# LED_Canton_Tower.net
KiCad netlist of a schematic drawn in EasyEDA
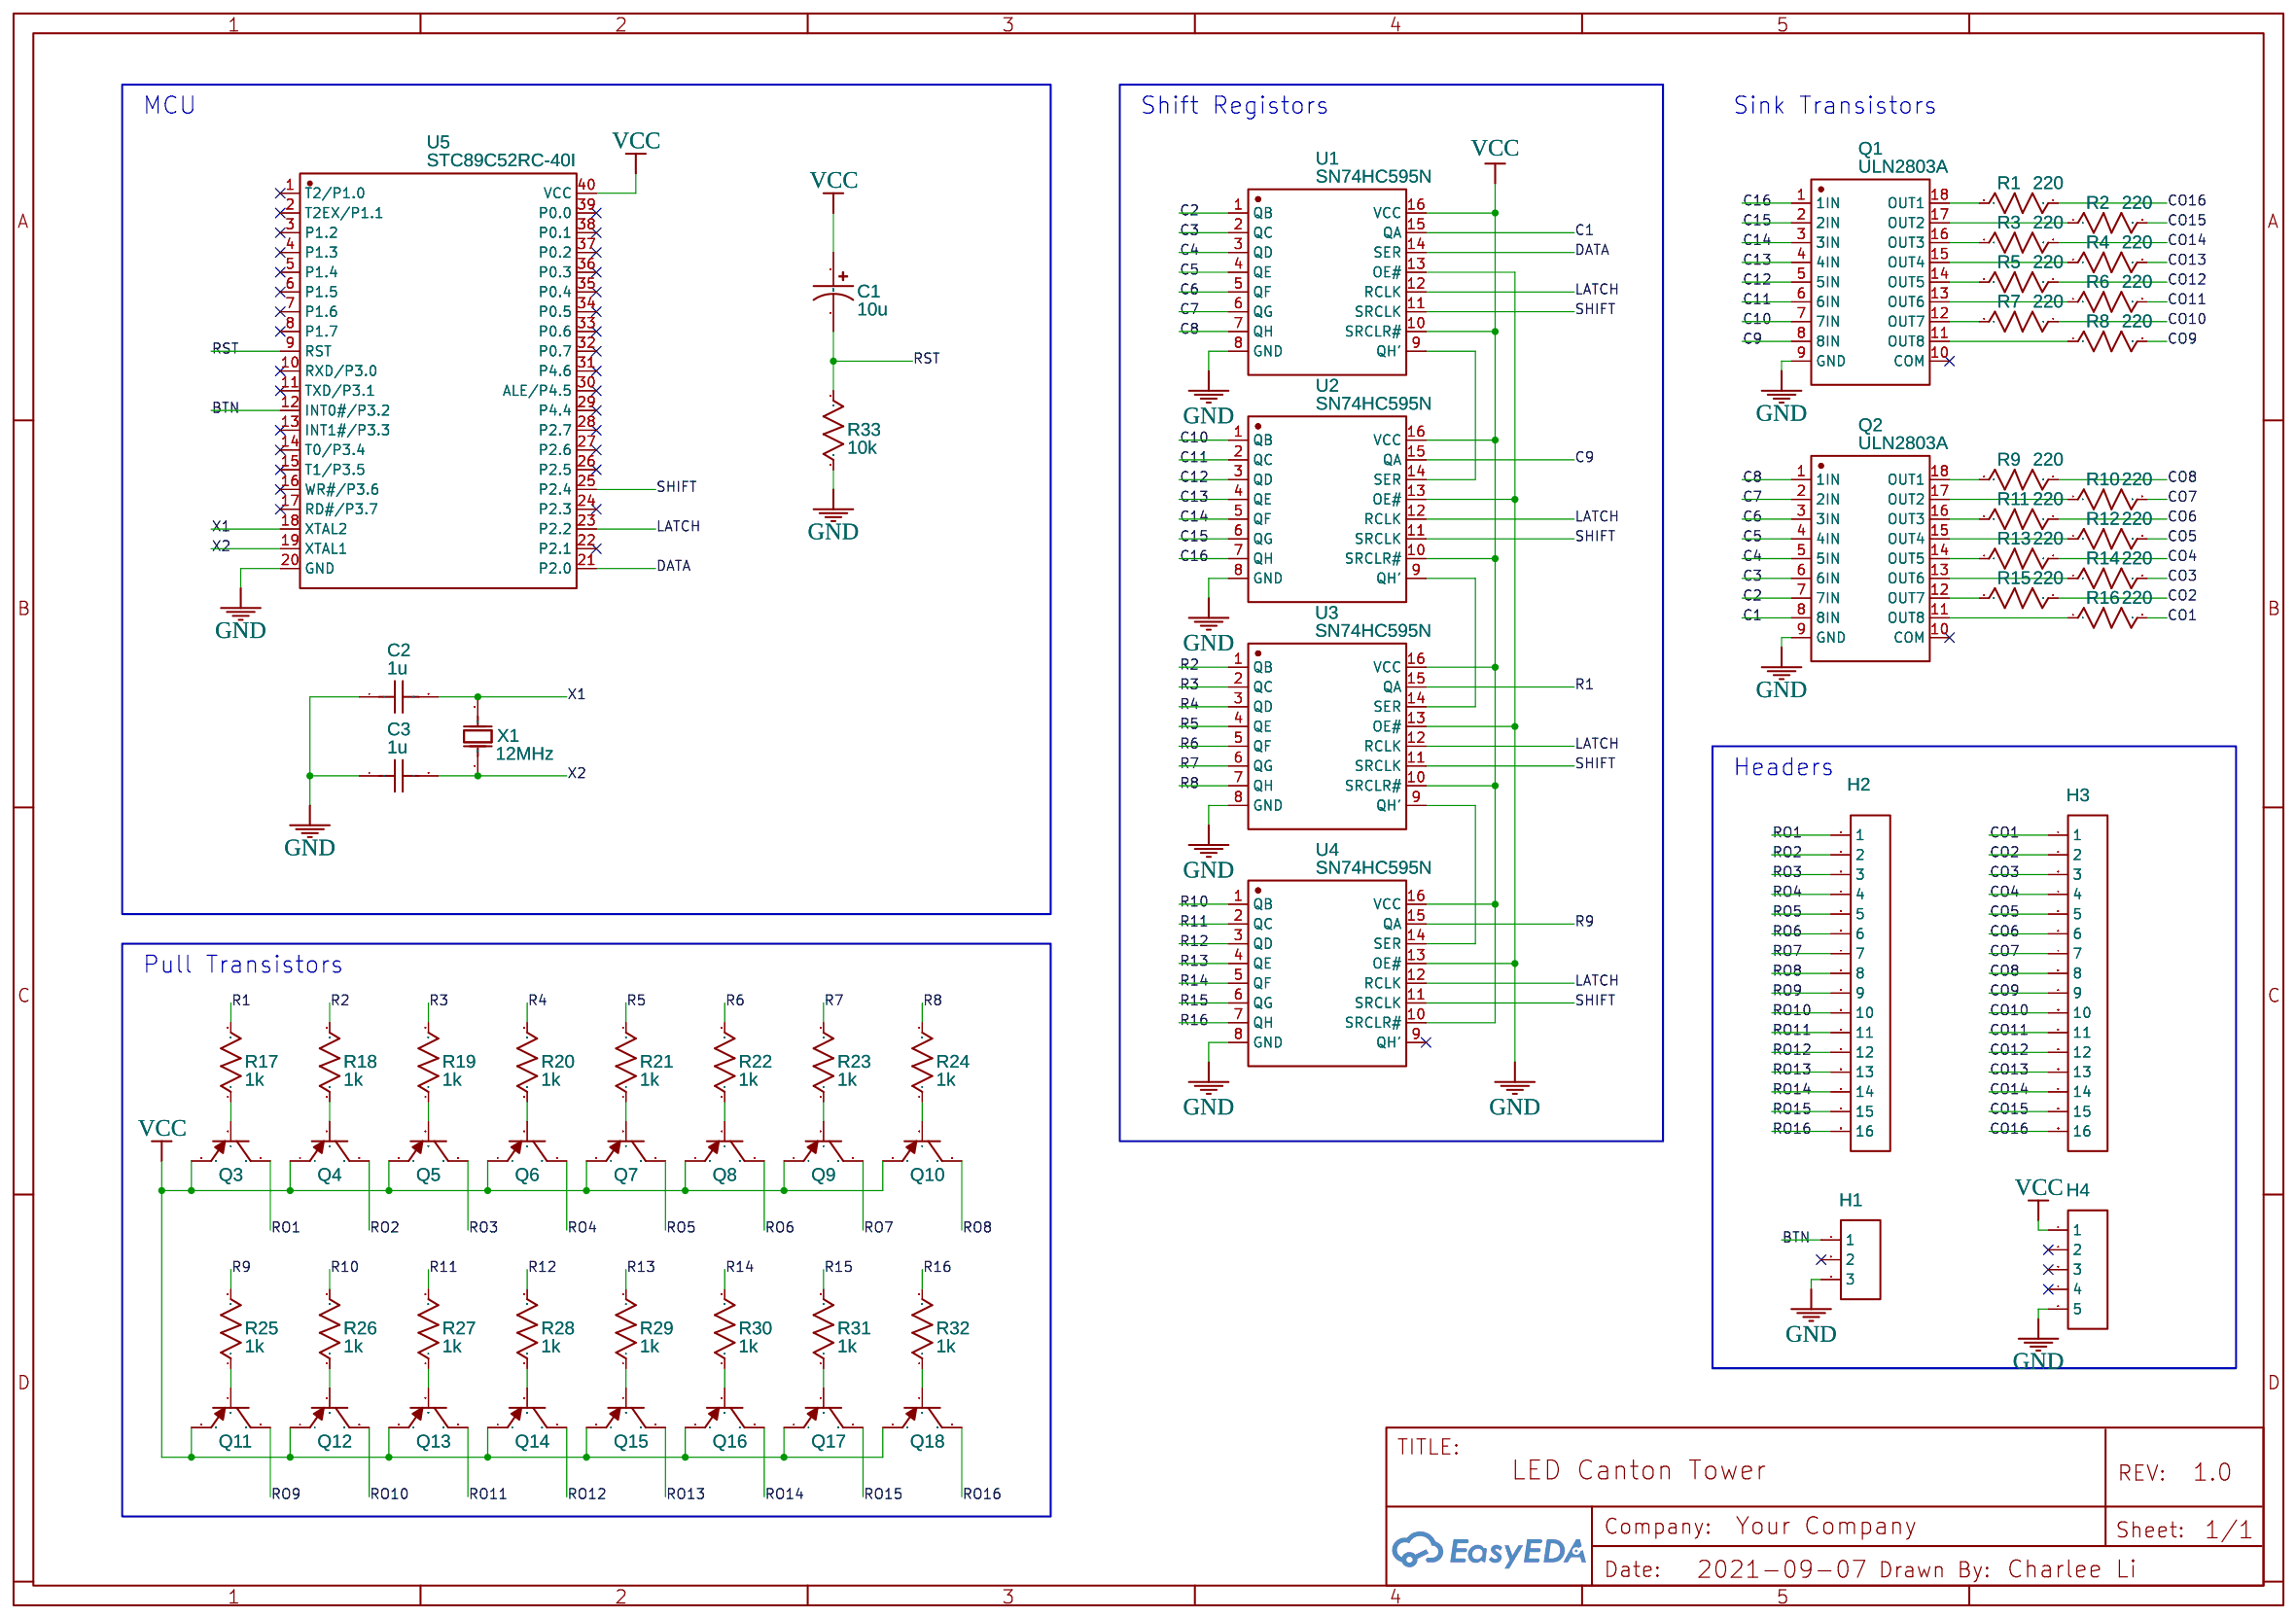
[diagram p0: schematic sheet]

(export (version "E")
  (design (tool "Eeschema 10.0.6"))
  (components
    (comp (ref "C1") (value "10u") (libsource (lib "") (part "CE_TH_D3.0×F1.5_US")))
    (comp (ref "C2") (value "1u") (libsource (lib "") (part "C_RAD-0.1_US")))
    (comp (ref "C3") (value "1u") (libsource (lib "") (part "C_RAD-0.1_US")))
    (comp (ref "H1")
      (value "HDR-F-2.54_1x3")
      (fields (field (name "BOM_Supplier Part") "C146690"))
      (libsource (lib "") (part "HDR-F-2.54_1x3"))
    )
    (comp (ref "H2")
      (value "HDR-F-2.54_1x16")
      (fields (field (name "BOM_Supplier Part") "C66987"))
      (libsource (lib "") (part "HDR-F-2.54_1x16"))
    )
    (comp (ref "H3")
      (value "HDR-F-2.54_1x16")
      (fields (field (name "BOM_Supplier Part") "C66987"))
      (libsource (lib "") (part "HDR-F-2.54_1x16"))
    )
    (comp (ref "H4")
      (value "HDR-F-2.54_1x5")
      (fields (field (name "BOM_Supplier Part") "C50950"))
      (libsource (lib "") (part "HDR-F-2.54_1x5"))
    )
    (comp (ref "Q1")
      (value "ULN2803A")
      (fields (field (name "BOM_Supplier Part") "C73936"))
      (libsource (lib "") (part "ULN2803A"))
    )
    (comp (ref "Q2")
      (value "ULN2803A")
      (fields (field (name "BOM_Supplier Part") "C73936"))
      (libsource (lib "") (part "ULN2803A"))
    )
    (comp (ref "Q3")
      (value "2N3906(TO-92)")
      (fields (field (name "BOM_Manufacturer Part") "2N3906") (field (name "BOM_Supplier Part") "C9809"))
      (libsource (lib "") (part "2N3906(TO-92)"))
    )
    (comp (ref "Q4")
      (value "2N3906(TO-92)")
      (fields (field (name "BOM_Manufacturer Part") "2N3906") (field (name "BOM_Supplier Part") "C9809"))
      (libsource (lib "") (part "2N3906(TO-92)"))
    )
    (comp (ref "Q5")
      (value "2N3906(TO-92)")
      (fields (field (name "BOM_Manufacturer Part") "2N3906") (field (name "BOM_Supplier Part") "C9809"))
      (libsource (lib "") (part "2N3906(TO-92)"))
    )
    (comp (ref "Q6")
      (value "2N3906(TO-92)")
      (fields (field (name "BOM_Manufacturer Part") "2N3906") (field (name "BOM_Supplier Part") "C9809"))
      (libsource (lib "") (part "2N3906(TO-92)"))
    )
    (comp (ref "Q7")
      (value "2N3906(TO-92)")
      (fields (field (name "BOM_Manufacturer Part") "2N3906") (field (name "BOM_Supplier Part") "C9809"))
      (libsource (lib "") (part "2N3906(TO-92)"))
    )
    (comp (ref "Q8")
      (value "2N3906(TO-92)")
      (fields (field (name "BOM_Manufacturer Part") "2N3906") (field (name "BOM_Supplier Part") "C9809"))
      (libsource (lib "") (part "2N3906(TO-92)"))
    )
    (comp (ref "Q9")
      (value "2N3906(TO-92)")
      (fields (field (name "BOM_Manufacturer Part") "2N3906") (field (name "BOM_Supplier Part") "C9809"))
      (libsource (lib "") (part "2N3906(TO-92)"))
    )
    (comp (ref "Q10")
      (value "2N3906(TO-92)")
      (fields (field (name "BOM_Manufacturer Part") "2N3906") (field (name "BOM_Supplier Part") "C9809"))
      (libsource (lib "") (part "2N3906(TO-92)"))
    )
    (comp (ref "Q11")
      (value "2N3906(TO-92)")
      (fields (field (name "BOM_Manufacturer Part") "2N3906") (field (name "BOM_Supplier Part") "C9809"))
      (libsource (lib "") (part "2N3906(TO-92)"))
    )
    (comp (ref "Q12")
      (value "2N3906(TO-92)")
      (fields (field (name "BOM_Manufacturer Part") "2N3906") (field (name "BOM_Supplier Part") "C9809"))
      (libsource (lib "") (part "2N3906(TO-92)"))
    )
    (comp (ref "Q13")
      (value "2N3906(TO-92)")
      (fields (field (name "BOM_Manufacturer Part") "2N3906") (field (name "BOM_Supplier Part") "C9809"))
      (libsource (lib "") (part "2N3906(TO-92)"))
    )
    (comp (ref "Q14")
      (value "2N3906(TO-92)")
      (fields (field (name "BOM_Manufacturer Part") "2N3906") (field (name "BOM_Supplier Part") "C9809"))
      (libsource (lib "") (part "2N3906(TO-92)"))
    )
    (comp (ref "Q15")
      (value "2N3906(TO-92)")
      (fields (field (name "BOM_Manufacturer Part") "2N3906") (field (name "BOM_Supplier Part") "C9809"))
      (libsource (lib "") (part "2N3906(TO-92)"))
    )
    (comp (ref "Q16")
      (value "2N3906(TO-92)")
      (fields (field (name "BOM_Manufacturer Part") "2N3906") (field (name "BOM_Supplier Part") "C9809"))
      (libsource (lib "") (part "2N3906(TO-92)"))
    )
    (comp (ref "Q17")
      (value "2N3906(TO-92)")
      (fields (field (name "BOM_Manufacturer Part") "2N3906") (field (name "BOM_Supplier Part") "C9809"))
      (libsource (lib "") (part "2N3906(TO-92)"))
    )
    (comp (ref "Q18")
      (value "2N3906(TO-92)")
      (fields (field (name "BOM_Manufacturer Part") "2N3906") (field (name "BOM_Supplier Part") "C9809"))
      (libsource (lib "") (part "2N3906(TO-92)"))
    )
    (comp (ref "R1") (value "220") (libsource (lib "") (part "R_AXIAL-0.3_US")))
    (comp (ref "R2") (value "220") (libsource (lib "") (part "R_AXIAL-0.3_US")))
    (comp (ref "R3") (value "220") (libsource (lib "") (part "R_AXIAL-0.3_US")))
    (comp (ref "R4") (value "220") (libsource (lib "") (part "R_AXIAL-0.3_US")))
    (comp (ref "R5") (value "220") (libsource (lib "") (part "R_AXIAL-0.3_US")))
    (comp (ref "R6") (value "220") (libsource (lib "") (part "R_AXIAL-0.3_US")))
    (comp (ref "R7") (value "220") (libsource (lib "") (part "R_AXIAL-0.3_US")))
    (comp (ref "R8") (value "220") (libsource (lib "") (part "R_AXIAL-0.3_US")))
    (comp (ref "R9") (value "220") (libsource (lib "") (part "R_AXIAL-0.3_US")))
    (comp (ref "R10") (value "220") (libsource (lib "") (part "R_AXIAL-0.3_US")))
    (comp (ref "R11") (value "220") (libsource (lib "") (part "R_AXIAL-0.3_US")))
    (comp (ref "R12") (value "220") (libsource (lib "") (part "R_AXIAL-0.3_US")))
    (comp (ref "R13") (value "220") (libsource (lib "") (part "R_AXIAL-0.3_US")))
    (comp (ref "R14") (value "220") (libsource (lib "") (part "R_AXIAL-0.3_US")))
    (comp (ref "R15") (value "220") (libsource (lib "") (part "R_AXIAL-0.3_US")))
    (comp (ref "R16") (value "220") (libsource (lib "") (part "R_AXIAL-0.3_US")))
    (comp (ref "R17") (value "1k") (libsource (lib "") (part "R_AXIAL-0.3_US_1")))
    (comp (ref "R18") (value "1k") (libsource (lib "") (part "R_AXIAL-0.3_US_1")))
    (comp (ref "R19") (value "1k") (libsource (lib "") (part "R_AXIAL-0.3_US_1")))
    (comp (ref "R20") (value "1k") (libsource (lib "") (part "R_AXIAL-0.3_US_1")))
    (comp (ref "R21") (value "1k") (libsource (lib "") (part "R_AXIAL-0.3_US_1")))
    (comp (ref "R22") (value "1k") (libsource (lib "") (part "R_AXIAL-0.3_US_1")))
    (comp (ref "R23") (value "1k") (libsource (lib "") (part "R_AXIAL-0.3_US_1")))
    (comp (ref "R24") (value "1k") (libsource (lib "") (part "R_AXIAL-0.3_US_1")))
    (comp (ref "R25") (value "1k") (libsource (lib "") (part "R_AXIAL-0.3_US_1")))
    (comp (ref "R26") (value "1k") (libsource (lib "") (part "R_AXIAL-0.3_US_1")))
    (comp (ref "R27") (value "1k") (libsource (lib "") (part "R_AXIAL-0.3_US_1")))
    (comp (ref "R28") (value "1k") (libsource (lib "") (part "R_AXIAL-0.3_US_1")))
    (comp (ref "R29") (value "1k") (libsource (lib "") (part "R_AXIAL-0.3_US_1")))
    (comp (ref "R30") (value "1k") (libsource (lib "") (part "R_AXIAL-0.3_US_1")))
    (comp (ref "R31") (value "1k") (libsource (lib "") (part "R_AXIAL-0.3_US_1")))
    (comp (ref "R32") (value "1k") (libsource (lib "") (part "R_AXIAL-0.3_US_1")))
    (comp (ref "R33") (value "10k") (libsource (lib "") (part "R_AXIAL-0.3_US_1")))
    (comp (ref "U1")
      (value "SN74HC595N")
      (fields (field (name "BOM_Supplier Part") "C78711"))
      (libsource (lib "") (part "SN74HC595N"))
    )
    (comp (ref "U2")
      (value "SN74HC595N")
      (fields (field (name "BOM_Supplier Part") "C78711"))
      (libsource (lib "") (part "SN74HC595N"))
    )
    (comp (ref "U3")
      (value "SN74HC595N")
      (fields (field (name "BOM_Supplier Part") "C78711"))
      (libsource (lib "") (part "SN74HC595N"))
    )
    (comp (ref "U4")
      (value "SN74HC595N")
      (fields (field (name "BOM_Supplier Part") "C78711"))
      (libsource (lib "") (part "SN74HC595N"))
    )
    (comp (ref "U5")
      (value "STC89C52RC-40I")
      (fields (field (name "BOM_Supplier Part") "C14022"))
      (libsource (lib "") (part "STC89C52RC-40I"))
    )
    (comp (ref "X1")
      (value "12MHz")
      (fields
        (field (name "BOM_Manufacturer Part") "X49UD12MSD2SC")
        (field (name "BOM_Supplier Part") "C2188")
      )
      (libsource (lib "") (part "X49UD12MSD2SC"))
    )
  )
  (nets
    (net (code "1") (name "/BTN") (class "Default")
      (node (ref "H1") (pin "1") (pinfunction "1_1") (pintype "input"))
      (node (ref "U5") (pin "12") (pinfunction "INT0#/P3.2_12") (pintype "unspecified"))
    )
    (net (code "2") (name "/C1") (class "Default")
      (node (ref "Q2") (pin "8") (pinfunction "8IN_8") (pintype "unspecified"))
      (node (ref "U1") (pin "15") (pinfunction "QA_15") (pintype "unspecified"))
    )
    (net (code "3") (name "/C2") (class "Default")
      (node (ref "Q2") (pin "7") (pinfunction "7IN_7") (pintype "unspecified"))
      (node (ref "U1") (pin "1") (pinfunction "QB_1") (pintype "unspecified"))
    )
    (net (code "4") (name "/C3") (class "Default")
      (node (ref "Q2") (pin "6") (pinfunction "6IN_6") (pintype "unspecified"))
      (node (ref "U1") (pin "2") (pinfunction "QC_2") (pintype "unspecified"))
    )
    (net (code "5") (name "/C4") (class "Default")
      (node (ref "Q2") (pin "5") (pinfunction "5IN_5") (pintype "unspecified"))
      (node (ref "U1") (pin "3") (pinfunction "QD_3") (pintype "unspecified"))
    )
    (net (code "6") (name "/C5") (class "Default")
      (node (ref "Q2") (pin "4") (pinfunction "4IN_4") (pintype "unspecified"))
      (node (ref "U1") (pin "4") (pinfunction "QE_4") (pintype "unspecified"))
    )
    (net (code "7") (name "/C6") (class "Default")
      (node (ref "Q2") (pin "3") (pinfunction "3IN_3") (pintype "unspecified"))
      (node (ref "U1") (pin "5") (pinfunction "QF_5") (pintype "unspecified"))
    )
    (net (code "8") (name "/C7") (class "Default")
      (node (ref "Q2") (pin "2") (pinfunction "2IN_2") (pintype "unspecified"))
      (node (ref "U1") (pin "6") (pinfunction "QG_6") (pintype "unspecified"))
    )
    (net (code "9") (name "/C8") (class "Default")
      (node (ref "Q2") (pin "1") (pinfunction "1IN_1") (pintype "unspecified"))
      (node (ref "U1") (pin "7") (pinfunction "QH_7") (pintype "unspecified"))
    )
    (net (code "10") (name "/C9") (class "Default")
      (node (ref "Q1") (pin "8") (pinfunction "8IN_8") (pintype "unspecified"))
      (node (ref "U2") (pin "15") (pinfunction "QA_15") (pintype "unspecified"))
    )
    (net (code "11") (name "/C10") (class "Default")
      (node (ref "Q1") (pin "7") (pinfunction "7IN_7") (pintype "unspecified"))
      (node (ref "U2") (pin "1") (pinfunction "QB_1") (pintype "unspecified"))
    )
    (net (code "12") (name "/C11") (class "Default")
      (node (ref "Q1") (pin "6") (pinfunction "6IN_6") (pintype "unspecified"))
      (node (ref "U2") (pin "2") (pinfunction "QC_2") (pintype "unspecified"))
    )
    (net (code "13") (name "/C12") (class "Default")
      (node (ref "Q1") (pin "5") (pinfunction "5IN_5") (pintype "unspecified"))
      (node (ref "U2") (pin "3") (pinfunction "QD_3") (pintype "unspecified"))
    )
    (net (code "14") (name "/C13") (class "Default")
      (node (ref "Q1") (pin "4") (pinfunction "4IN_4") (pintype "unspecified"))
      (node (ref "U2") (pin "4") (pinfunction "QE_4") (pintype "unspecified"))
    )
    (net (code "15") (name "/C14") (class "Default")
      (node (ref "Q1") (pin "3") (pinfunction "3IN_3") (pintype "unspecified"))
      (node (ref "U2") (pin "5") (pinfunction "QF_5") (pintype "unspecified"))
    )
    (net (code "16") (name "/C15") (class "Default")
      (node (ref "Q1") (pin "2") (pinfunction "2IN_2") (pintype "unspecified"))
      (node (ref "U2") (pin "6") (pinfunction "QG_6") (pintype "unspecified"))
    )
    (net (code "17") (name "/C16") (class "Default")
      (node (ref "Q1") (pin "1") (pinfunction "1IN_1") (pintype "unspecified"))
      (node (ref "U2") (pin "7") (pinfunction "QH_7") (pintype "unspecified"))
    )
    (net (code "18") (name "/CO1") (class "Default")
      (node (ref "H3") (pin "1") (pinfunction "1_1") (pintype "unspecified"))
      (node (ref "R16") (pin "2") (pinfunction "2_2") (pintype "unspecified"))
    )
    (net (code "19") (name "/CO2") (class "Default")
      (node (ref "H3") (pin "2") (pinfunction "2_2") (pintype "unspecified"))
      (node (ref "R15") (pin "2") (pinfunction "2_2") (pintype "unspecified"))
    )
    (net (code "20") (name "/CO3") (class "Default")
      (node (ref "H3") (pin "3") (pinfunction "3_3") (pintype "unspecified"))
      (node (ref "R14") (pin "2") (pinfunction "2_2") (pintype "unspecified"))
    )
    (net (code "21") (name "/CO4") (class "Default")
      (node (ref "H3") (pin "4") (pinfunction "4_4") (pintype "unspecified"))
      (node (ref "R13") (pin "2") (pinfunction "2_2") (pintype "unspecified"))
    )
    (net (code "22") (name "/CO5") (class "Default")
      (node (ref "H3") (pin "5") (pinfunction "5_5") (pintype "unspecified"))
      (node (ref "R12") (pin "2") (pinfunction "2_2") (pintype "unspecified"))
    )
    (net (code "23") (name "/CO6") (class "Default")
      (node (ref "H3") (pin "6") (pinfunction "6_6") (pintype "unspecified"))
      (node (ref "R11") (pin "2") (pinfunction "2_2") (pintype "unspecified"))
    )
    (net (code "24") (name "/CO7") (class "Default")
      (node (ref "H3") (pin "7") (pinfunction "7_7") (pintype "unspecified"))
      (node (ref "R10") (pin "2") (pinfunction "2_2") (pintype "unspecified"))
    )
    (net (code "25") (name "/CO8") (class "Default")
      (node (ref "H3") (pin "8") (pinfunction "8_8") (pintype "unspecified"))
      (node (ref "R9") (pin "2") (pinfunction "2_2") (pintype "unspecified"))
    )
    (net (code "26") (name "/CO9") (class "Default")
      (node (ref "H3") (pin "9") (pinfunction "9_9") (pintype "unspecified"))
      (node (ref "R8") (pin "2") (pinfunction "2_2") (pintype "unspecified"))
    )
    (net (code "27") (name "/CO10") (class "Default")
      (node (ref "H3") (pin "10") (pinfunction "10_10") (pintype "unspecified"))
      (node (ref "R7") (pin "2") (pinfunction "2_2") (pintype "unspecified"))
    )
    (net (code "28") (name "/CO11") (class "Default")
      (node (ref "H3") (pin "11") (pinfunction "11_11") (pintype "unspecified"))
      (node (ref "R6") (pin "2") (pinfunction "2_2") (pintype "unspecified"))
    )
    (net (code "29") (name "/CO12") (class "Default")
      (node (ref "H3") (pin "12") (pinfunction "12_12") (pintype "unspecified"))
      (node (ref "R5") (pin "2") (pinfunction "2_2") (pintype "unspecified"))
    )
    (net (code "30") (name "/CO13") (class "Default")
      (node (ref "H3") (pin "13") (pinfunction "13_13") (pintype "unspecified"))
      (node (ref "R4") (pin "2") (pinfunction "2_2") (pintype "unspecified"))
    )
    (net (code "31") (name "/CO14") (class "Default")
      (node (ref "H3") (pin "14") (pinfunction "14_14") (pintype "unspecified"))
      (node (ref "R3") (pin "2") (pinfunction "2_2") (pintype "unspecified"))
    )
    (net (code "32") (name "/CO15") (class "Default")
      (node (ref "H3") (pin "15") (pinfunction "15_15") (pintype "unspecified"))
      (node (ref "R2") (pin "2") (pinfunction "2_2") (pintype "unspecified"))
    )
    (net (code "33") (name "/CO16") (class "Default")
      (node (ref "H3") (pin "16") (pinfunction "16_16") (pintype "unspecified"))
      (node (ref "R1") (pin "2") (pinfunction "2_2") (pintype "unspecified"))
    )
    (net (code "34") (name "/DATA") (class "Default")
      (node (ref "U1") (pin "14") (pinfunction "SER_14") (pintype "unspecified"))
      (node (ref "U5") (pin "21") (pinfunction "P2.0_21") (pintype "unspecified"))
    )
    (net (code "35") (name "/LATCH") (class "Default")
      (node (ref "U1") (pin "12") (pinfunction "RCLK_12") (pintype "unspecified"))
      (node (ref "U2") (pin "12") (pinfunction "RCLK_12") (pintype "unspecified"))
      (node (ref "U3") (pin "12") (pinfunction "RCLK_12") (pintype "unspecified"))
      (node (ref "U4") (pin "12") (pinfunction "RCLK_12") (pintype "unspecified"))
      (node (ref "U5") (pin "23") (pinfunction "P2.2_23") (pintype "unspecified"))
    )
    (net (code "36") (name "/R1") (class "Default")
      (node (ref "R17") (pin "2") (pinfunction "2_2") (pintype "unspecified"))
      (node (ref "U3") (pin "15") (pinfunction "QA_15") (pintype "unspecified"))
    )
    (net (code "37") (name "/R2") (class "Default")
      (node (ref "R18") (pin "2") (pinfunction "2_2") (pintype "unspecified"))
      (node (ref "U3") (pin "1") (pinfunction "QB_1") (pintype "unspecified"))
    )
    (net (code "38") (name "/R3") (class "Default")
      (node (ref "R19") (pin "2") (pinfunction "2_2") (pintype "unspecified"))
      (node (ref "U3") (pin "2") (pinfunction "QC_2") (pintype "unspecified"))
    )
    (net (code "39") (name "/R4") (class "Default")
      (node (ref "R20") (pin "2") (pinfunction "2_2") (pintype "unspecified"))
      (node (ref "U3") (pin "3") (pinfunction "QD_3") (pintype "unspecified"))
    )
    (net (code "40") (name "/R5") (class "Default")
      (node (ref "R21") (pin "2") (pinfunction "2_2") (pintype "unspecified"))
      (node (ref "U3") (pin "4") (pinfunction "QE_4") (pintype "unspecified"))
    )
    (net (code "41") (name "/R6") (class "Default")
      (node (ref "R22") (pin "2") (pinfunction "2_2") (pintype "unspecified"))
      (node (ref "U3") (pin "5") (pinfunction "QF_5") (pintype "unspecified"))
    )
    (net (code "42") (name "/R7") (class "Default")
      (node (ref "R23") (pin "2") (pinfunction "2_2") (pintype "unspecified"))
      (node (ref "U3") (pin "6") (pinfunction "QG_6") (pintype "unspecified"))
    )
    (net (code "43") (name "/R8") (class "Default")
      (node (ref "R24") (pin "2") (pinfunction "2_2") (pintype "unspecified"))
      (node (ref "U3") (pin "7") (pinfunction "QH_7") (pintype "unspecified"))
    )
    (net (code "44") (name "/R9") (class "Default")
      (node (ref "R25") (pin "2") (pinfunction "2_2") (pintype "unspecified"))
      (node (ref "U4") (pin "15") (pinfunction "QA_15") (pintype "unspecified"))
    )
    (net (code "45") (name "/R10") (class "Default")
      (node (ref "R26") (pin "2") (pinfunction "2_2") (pintype "unspecified"))
      (node (ref "U4") (pin "1") (pinfunction "QB_1") (pintype "unspecified"))
    )
    (net (code "46") (name "/R11") (class "Default")
      (node (ref "R27") (pin "2") (pinfunction "2_2") (pintype "unspecified"))
      (node (ref "U4") (pin "2") (pinfunction "QC_2") (pintype "unspecified"))
    )
    (net (code "47") (name "/R12") (class "Default")
      (node (ref "R28") (pin "2") (pinfunction "2_2") (pintype "unspecified"))
      (node (ref "U4") (pin "3") (pinfunction "QD_3") (pintype "unspecified"))
    )
    (net (code "48") (name "/R13") (class "Default")
      (node (ref "R29") (pin "2") (pinfunction "2_2") (pintype "unspecified"))
      (node (ref "U4") (pin "4") (pinfunction "QE_4") (pintype "unspecified"))
    )
    (net (code "49") (name "/R14") (class "Default")
      (node (ref "R30") (pin "2") (pinfunction "2_2") (pintype "unspecified"))
      (node (ref "U4") (pin "5") (pinfunction "QF_5") (pintype "unspecified"))
    )
    (net (code "50") (name "/R15") (class "Default")
      (node (ref "R31") (pin "2") (pinfunction "2_2") (pintype "unspecified"))
      (node (ref "U4") (pin "6") (pinfunction "QG_6") (pintype "unspecified"))
    )
    (net (code "51") (name "/R16") (class "Default")
      (node (ref "R32") (pin "2") (pinfunction "2_2") (pintype "unspecified"))
      (node (ref "U4") (pin "7") (pinfunction "QH_7") (pintype "unspecified"))
    )
    (net (code "52") (name "/RO1") (class "Default")
      (node (ref "H2") (pin "1") (pinfunction "1_1") (pintype "unspecified"))
      (node (ref "Q3") (pin "3") (pinfunction "C_3") (pintype "input"))
    )
    (net (code "53") (name "/RO2") (class "Default")
      (node (ref "H2") (pin "2") (pinfunction "2_2") (pintype "unspecified"))
      (node (ref "Q4") (pin "3") (pinfunction "C_3") (pintype "input"))
    )
    (net (code "54") (name "/RO3") (class "Default")
      (node (ref "H2") (pin "3") (pinfunction "3_3") (pintype "unspecified"))
      (node (ref "Q5") (pin "3") (pinfunction "C_3") (pintype "input"))
    )
    (net (code "55") (name "/RO4") (class "Default")
      (node (ref "H2") (pin "4") (pinfunction "4_4") (pintype "unspecified"))
      (node (ref "Q6") (pin "3") (pinfunction "C_3") (pintype "input"))
    )
    (net (code "56") (name "/RO5") (class "Default")
      (node (ref "H2") (pin "5") (pinfunction "5_5") (pintype "unspecified"))
      (node (ref "Q7") (pin "3") (pinfunction "C_3") (pintype "input"))
    )
    (net (code "57") (name "/RO6") (class "Default")
      (node (ref "H2") (pin "6") (pinfunction "6_6") (pintype "unspecified"))
      (node (ref "Q8") (pin "3") (pinfunction "C_3") (pintype "input"))
    )
    (net (code "58") (name "/RO7") (class "Default")
      (node (ref "H2") (pin "7") (pinfunction "7_7") (pintype "unspecified"))
      (node (ref "Q9") (pin "3") (pinfunction "C_3") (pintype "input"))
    )
    (net (code "59") (name "/RO8") (class "Default")
      (node (ref "H2") (pin "8") (pinfunction "8_8") (pintype "unspecified"))
      (node (ref "Q10") (pin "3") (pinfunction "C_3") (pintype "input"))
    )
    (net (code "60") (name "/RO9") (class "Default")
      (node (ref "H2") (pin "9") (pinfunction "9_9") (pintype "unspecified"))
      (node (ref "Q11") (pin "3") (pinfunction "C_3") (pintype "input"))
    )
    (net (code "61") (name "/RO10") (class "Default")
      (node (ref "H2") (pin "10") (pinfunction "10_10") (pintype "unspecified"))
      (node (ref "Q12") (pin "3") (pinfunction "C_3") (pintype "input"))
    )
    (net (code "62") (name "/RO11") (class "Default")
      (node (ref "H2") (pin "11") (pinfunction "11_11") (pintype "unspecified"))
      (node (ref "Q13") (pin "3") (pinfunction "C_3") (pintype "input"))
    )
    (net (code "63") (name "/RO12") (class "Default")
      (node (ref "H2") (pin "12") (pinfunction "12_12") (pintype "unspecified"))
      (node (ref "Q14") (pin "3") (pinfunction "C_3") (pintype "input"))
    )
    (net (code "64") (name "/RO13") (class "Default")
      (node (ref "H2") (pin "13") (pinfunction "13_13") (pintype "unspecified"))
      (node (ref "Q15") (pin "3") (pinfunction "C_3") (pintype "input"))
    )
    (net (code "65") (name "/RO14") (class "Default")
      (node (ref "H2") (pin "14") (pinfunction "14_14") (pintype "unspecified"))
      (node (ref "Q16") (pin "3") (pinfunction "C_3") (pintype "input"))
    )
    (net (code "66") (name "/RO15") (class "Default")
      (node (ref "H2") (pin "15") (pinfunction "15_15") (pintype "unspecified"))
      (node (ref "Q17") (pin "3") (pinfunction "C_3") (pintype "input"))
    )
    (net (code "67") (name "/RO16") (class "Default")
      (node (ref "H2") (pin "16") (pinfunction "16_16") (pintype "unspecified"))
      (node (ref "Q18") (pin "3") (pinfunction "C_3") (pintype "input"))
    )
    (net (code "68") (name "/RST") (class "Default")
      (node (ref "C1") (pin "2") (pinfunction "2_2") (pintype "unspecified"))
      (node (ref "R33") (pin "2") (pinfunction "2_2") (pintype "unspecified"))
      (node (ref "U5") (pin "9") (pinfunction "RST_9") (pintype "unspecified"))
    )
    (net (code "69") (name "/SHIFT") (class "Default")
      (node (ref "U1") (pin "11") (pinfunction "SRCLK_11") (pintype "unspecified"))
      (node (ref "U2") (pin "11") (pinfunction "SRCLK_11") (pintype "unspecified"))
      (node (ref "U3") (pin "11") (pinfunction "SRCLK_11") (pintype "unspecified"))
      (node (ref "U4") (pin "11") (pinfunction "SRCLK_11") (pintype "unspecified"))
      (node (ref "U5") (pin "25") (pinfunction "P2.4_25") (pintype "unspecified"))
    )
    (net (code "70") (name "/X1") (class "Default")
      (node (ref "C2") (pin "2") (pinfunction "2_2") (pintype "unspecified"))
      (node (ref "U5") (pin "18") (pinfunction "XTAL2_18") (pintype "unspecified"))
      (node (ref "X1") (pin "2") (pinfunction "OSC2_2") (pintype "input"))
    )
    (net (code "71") (name "/X2") (class "Default")
      (node (ref "C3") (pin "2") (pinfunction "2_2") (pintype "unspecified"))
      (node (ref "U5") (pin "19") (pinfunction "XTAL1_19") (pintype "unspecified"))
      (node (ref "X1") (pin "1") (pinfunction "OSC1_1") (pintype "input"))
    )
    (net (code "72") (name "GND") (class "Default")
      (node (ref "C2") (pin "1") (pinfunction "1_1") (pintype "unspecified"))
      (node (ref "C3") (pin "1") (pinfunction "1_1") (pintype "unspecified"))
      (node (ref "H1") (pin "3") (pinfunction "3_3") (pintype "input"))
      (node (ref "H4") (pin "5") (pinfunction "5_5") (pintype "unspecified"))
      (node (ref "Q1") (pin "9") (pinfunction "GND_9") (pintype "unspecified"))
      (node (ref "Q2") (pin "9") (pinfunction "GND_9") (pintype "unspecified"))
      (node (ref "R33") (pin "1") (pinfunction "1_1") (pintype "unspecified"))
      (node (ref "U1") (pin "13") (pinfunction "OE#_13") (pintype "unspecified"))
      (node (ref "U1") (pin "8") (pinfunction "GND_8") (pintype "unspecified"))
      (node (ref "U2") (pin "13") (pinfunction "OE#_13") (pintype "unspecified"))
      (node (ref "U2") (pin "8") (pinfunction "GND_8") (pintype "unspecified"))
      (node (ref "U3") (pin "13") (pinfunction "OE#_13") (pintype "unspecified"))
      (node (ref "U3") (pin "8") (pinfunction "GND_8") (pintype "unspecified"))
      (node (ref "U4") (pin "13") (pinfunction "OE#_13") (pintype "unspecified"))
      (node (ref "U4") (pin "8") (pinfunction "GND_8") (pintype "unspecified"))
      (node (ref "U5") (pin "20") (pinfunction "GND_20") (pintype "unspecified"))
    )
    (net (code "73") (name "Net-(Q1-OUT1)") (class "Default")
      (node (ref "Q1") (pin "18") (pinfunction "OUT1_18") (pintype "unspecified"))
      (node (ref "R1") (pin "1") (pinfunction "1_1") (pintype "unspecified"))
    )
    (net (code "74") (name "Net-(Q1-OUT2)") (class "Default")
      (node (ref "Q1") (pin "17") (pinfunction "OUT2_17") (pintype "unspecified"))
      (node (ref "R2") (pin "1") (pinfunction "1_1") (pintype "unspecified"))
    )
    (net (code "75") (name "Net-(Q1-OUT3)") (class "Default")
      (node (ref "Q1") (pin "16") (pinfunction "OUT3_16") (pintype "unspecified"))
      (node (ref "R3") (pin "1") (pinfunction "1_1") (pintype "unspecified"))
    )
    (net (code "76") (name "Net-(Q1-OUT4)") (class "Default")
      (node (ref "Q1") (pin "15") (pinfunction "OUT4_15") (pintype "unspecified"))
      (node (ref "R4") (pin "1") (pinfunction "1_1") (pintype "unspecified"))
    )
    (net (code "77") (name "Net-(Q1-OUT5)") (class "Default")
      (node (ref "Q1") (pin "14") (pinfunction "OUT5_14") (pintype "unspecified"))
      (node (ref "R5") (pin "1") (pinfunction "1_1") (pintype "unspecified"))
    )
    (net (code "78") (name "Net-(Q1-OUT6)") (class "Default")
      (node (ref "Q1") (pin "13") (pinfunction "OUT6_13") (pintype "unspecified"))
      (node (ref "R6") (pin "1") (pinfunction "1_1") (pintype "unspecified"))
    )
    (net (code "79") (name "Net-(Q1-OUT7)") (class "Default")
      (node (ref "Q1") (pin "12") (pinfunction "OUT7_12") (pintype "unspecified"))
      (node (ref "R7") (pin "1") (pinfunction "1_1") (pintype "unspecified"))
    )
    (net (code "80") (name "Net-(Q1-OUT8)") (class "Default")
      (node (ref "Q1") (pin "11") (pinfunction "OUT8_11") (pintype "unspecified"))
      (node (ref "R8") (pin "1") (pinfunction "1_1") (pintype "unspecified"))
    )
    (net (code "81") (name "Net-(Q2-OUT1)") (class "Default")
      (node (ref "Q2") (pin "18") (pinfunction "OUT1_18") (pintype "unspecified"))
      (node (ref "R9") (pin "1") (pinfunction "1_1") (pintype "unspecified"))
    )
    (net (code "82") (name "Net-(Q2-OUT2)") (class "Default")
      (node (ref "Q2") (pin "17") (pinfunction "OUT2_17") (pintype "unspecified"))
      (node (ref "R10") (pin "1") (pinfunction "1_1") (pintype "unspecified"))
    )
    (net (code "83") (name "Net-(Q2-OUT3)") (class "Default")
      (node (ref "Q2") (pin "16") (pinfunction "OUT3_16") (pintype "unspecified"))
      (node (ref "R11") (pin "1") (pinfunction "1_1") (pintype "unspecified"))
    )
    (net (code "84") (name "Net-(Q2-OUT4)") (class "Default")
      (node (ref "Q2") (pin "15") (pinfunction "OUT4_15") (pintype "unspecified"))
      (node (ref "R12") (pin "1") (pinfunction "1_1") (pintype "unspecified"))
    )
    (net (code "85") (name "Net-(Q2-OUT5)") (class "Default")
      (node (ref "Q2") (pin "14") (pinfunction "OUT5_14") (pintype "unspecified"))
      (node (ref "R13") (pin "1") (pinfunction "1_1") (pintype "unspecified"))
    )
    (net (code "86") (name "Net-(Q2-OUT6)") (class "Default")
      (node (ref "Q2") (pin "13") (pinfunction "OUT6_13") (pintype "unspecified"))
      (node (ref "R14") (pin "1") (pinfunction "1_1") (pintype "unspecified"))
    )
    (net (code "87") (name "Net-(Q2-OUT7)") (class "Default")
      (node (ref "Q2") (pin "12") (pinfunction "OUT7_12") (pintype "unspecified"))
      (node (ref "R15") (pin "1") (pinfunction "1_1") (pintype "unspecified"))
    )
    (net (code "88") (name "Net-(Q2-OUT8)") (class "Default")
      (node (ref "Q2") (pin "11") (pinfunction "OUT8_11") (pintype "unspecified"))
      (node (ref "R16") (pin "1") (pinfunction "1_1") (pintype "unspecified"))
    )
    (net (code "89") (name "Net-(Q3-B)") (class "Default")
      (node (ref "Q3") (pin "2") (pinfunction "B_2") (pintype "input"))
      (node (ref "R17") (pin "1") (pinfunction "1_1") (pintype "unspecified"))
    )
    (net (code "90") (name "Net-(Q4-B)") (class "Default")
      (node (ref "Q4") (pin "2") (pinfunction "B_2") (pintype "input"))
      (node (ref "R18") (pin "1") (pinfunction "1_1") (pintype "unspecified"))
    )
    (net (code "91") (name "Net-(Q5-B)") (class "Default")
      (node (ref "Q5") (pin "2") (pinfunction "B_2") (pintype "input"))
      (node (ref "R19") (pin "1") (pinfunction "1_1") (pintype "unspecified"))
    )
    (net (code "92") (name "Net-(Q6-B)") (class "Default")
      (node (ref "Q6") (pin "2") (pinfunction "B_2") (pintype "input"))
      (node (ref "R20") (pin "1") (pinfunction "1_1") (pintype "unspecified"))
    )
    (net (code "93") (name "Net-(Q7-B)") (class "Default")
      (node (ref "Q7") (pin "2") (pinfunction "B_2") (pintype "input"))
      (node (ref "R21") (pin "1") (pinfunction "1_1") (pintype "unspecified"))
    )
    (net (code "94") (name "Net-(Q8-B)") (class "Default")
      (node (ref "Q8") (pin "2") (pinfunction "B_2") (pintype "input"))
      (node (ref "R22") (pin "1") (pinfunction "1_1") (pintype "unspecified"))
    )
    (net (code "95") (name "Net-(Q9-B)") (class "Default")
      (node (ref "Q9") (pin "2") (pinfunction "B_2") (pintype "input"))
      (node (ref "R23") (pin "1") (pinfunction "1_1") (pintype "unspecified"))
    )
    (net (code "96") (name "Net-(Q10-B)") (class "Default")
      (node (ref "Q10") (pin "2") (pinfunction "B_2") (pintype "input"))
      (node (ref "R24") (pin "1") (pinfunction "1_1") (pintype "unspecified"))
    )
    (net (code "97") (name "Net-(Q11-B)") (class "Default")
      (node (ref "Q11") (pin "2") (pinfunction "B_2") (pintype "input"))
      (node (ref "R25") (pin "1") (pinfunction "1_1") (pintype "unspecified"))
    )
    (net (code "98") (name "Net-(Q12-B)") (class "Default")
      (node (ref "Q12") (pin "2") (pinfunction "B_2") (pintype "input"))
      (node (ref "R26") (pin "1") (pinfunction "1_1") (pintype "unspecified"))
    )
    (net (code "99") (name "Net-(Q13-B)") (class "Default")
      (node (ref "Q13") (pin "2") (pinfunction "B_2") (pintype "input"))
      (node (ref "R27") (pin "1") (pinfunction "1_1") (pintype "unspecified"))
    )
    (net (code "100") (name "Net-(Q14-B)") (class "Default")
      (node (ref "Q14") (pin "2") (pinfunction "B_2") (pintype "input"))
      (node (ref "R28") (pin "1") (pinfunction "1_1") (pintype "unspecified"))
    )
    (net (code "101") (name "Net-(Q15-B)") (class "Default")
      (node (ref "Q15") (pin "2") (pinfunction "B_2") (pintype "input"))
      (node (ref "R29") (pin "1") (pinfunction "1_1") (pintype "unspecified"))
    )
    (net (code "102") (name "Net-(Q16-B)") (class "Default")
      (node (ref "Q16") (pin "2") (pinfunction "B_2") (pintype "input"))
      (node (ref "R30") (pin "1") (pinfunction "1_1") (pintype "unspecified"))
    )
    (net (code "103") (name "Net-(Q17-B)") (class "Default")
      (node (ref "Q17") (pin "2") (pinfunction "B_2") (pintype "input"))
      (node (ref "R31") (pin "1") (pinfunction "1_1") (pintype "unspecified"))
    )
    (net (code "104") (name "Net-(Q18-B)") (class "Default")
      (node (ref "Q18") (pin "2") (pinfunction "B_2") (pintype "input"))
      (node (ref "R32") (pin "1") (pinfunction "1_1") (pintype "unspecified"))
    )
    (net (code "105") (name "Net-(U1-QH')") (class "Default")
      (node (ref "U1") (pin "9") (pinfunction "QH'_9") (pintype "unspecified"))
      (node (ref "U2") (pin "14") (pinfunction "SER_14") (pintype "unspecified"))
    )
    (net (code "106") (name "Net-(U2-QH')") (class "Default")
      (node (ref "U2") (pin "9") (pinfunction "QH'_9") (pintype "unspecified"))
      (node (ref "U3") (pin "14") (pinfunction "SER_14") (pintype "unspecified"))
    )
    (net (code "107") (name "Net-(U3-QH')") (class "Default")
      (node (ref "U3") (pin "9") (pinfunction "QH'_9") (pintype "unspecified"))
      (node (ref "U4") (pin "14") (pinfunction "SER_14") (pintype "unspecified"))
    )
    (net (code "108") (name "VCC") (class "Default")
      (node (ref "C1") (pin "1") (pinfunction "1_1") (pintype "unspecified"))
      (node (ref "H4") (pin "1") (pinfunction "1_1") (pintype "unspecified"))
      (node (ref "Q10") (pin "1") (pinfunction "E_1") (pintype "input"))
      (node (ref "Q11") (pin "1") (pinfunction "E_1") (pintype "input"))
      (node (ref "Q12") (pin "1") (pinfunction "E_1") (pintype "input"))
      (node (ref "Q13") (pin "1") (pinfunction "E_1") (pintype "input"))
      (node (ref "Q14") (pin "1") (pinfunction "E_1") (pintype "input"))
      (node (ref "Q15") (pin "1") (pinfunction "E_1") (pintype "input"))
      (node (ref "Q16") (pin "1") (pinfunction "E_1") (pintype "input"))
      (node (ref "Q17") (pin "1") (pinfunction "E_1") (pintype "input"))
      (node (ref "Q18") (pin "1") (pinfunction "E_1") (pintype "input"))
      (node (ref "Q3") (pin "1") (pinfunction "E_1") (pintype "input"))
      (node (ref "Q4") (pin "1") (pinfunction "E_1") (pintype "input"))
      (node (ref "Q5") (pin "1") (pinfunction "E_1") (pintype "input"))
      (node (ref "Q6") (pin "1") (pinfunction "E_1") (pintype "input"))
      (node (ref "Q7") (pin "1") (pinfunction "E_1") (pintype "input"))
      (node (ref "Q8") (pin "1") (pinfunction "E_1") (pintype "input"))
      (node (ref "Q9") (pin "1") (pinfunction "E_1") (pintype "input"))
      (node (ref "U1") (pin "10") (pinfunction "SRCLR#_10") (pintype "unspecified"))
      (node (ref "U1") (pin "16") (pinfunction "VCC_16") (pintype "unspecified"))
      (node (ref "U2") (pin "10") (pinfunction "SRCLR#_10") (pintype "unspecified"))
      (node (ref "U2") (pin "16") (pinfunction "VCC_16") (pintype "unspecified"))
      (node (ref "U3") (pin "10") (pinfunction "SRCLR#_10") (pintype "unspecified"))
      (node (ref "U3") (pin "16") (pinfunction "VCC_16") (pintype "unspecified"))
      (node (ref "U4") (pin "10") (pinfunction "SRCLR#_10") (pintype "unspecified"))
      (node (ref "U4") (pin "16") (pinfunction "VCC_16") (pintype "unspecified"))
      (node (ref "U5") (pin "40") (pinfunction "VCC_40") (pintype "unspecified"))
    )
    (net (code "109") (name "unconnected-(H1-Pad2)") (class "Default")
      (node (ref "H1") (pin "2") (pinfunction "2_2") (pintype "input+no_connect"))
    )
    (net (code "110") (name "unconnected-(H4-Pad2)") (class "Default")
      (node (ref "H4") (pin "2") (pinfunction "2_2") (pintype "unspecified+no_connect"))
    )
    (net (code "111") (name "unconnected-(H4-Pad3)") (class "Default")
      (node (ref "H4") (pin "3") (pinfunction "3_3") (pintype "unspecified+no_connect"))
    )
    (net (code "112") (name "unconnected-(H4-Pad4)") (class "Default")
      (node (ref "H4") (pin "4") (pinfunction "4_4") (pintype "unspecified+no_connect"))
    )
    (net (code "113") (name "unconnected-(Q1-COM-Pad10)") (class "Default")
      (node (ref "Q1") (pin "10") (pinfunction "COM_10") (pintype "unspecified+no_connect"))
    )
    (net (code "114") (name "unconnected-(Q2-COM-Pad10)") (class "Default")
      (node (ref "Q2") (pin "10") (pinfunction "COM_10") (pintype "unspecified+no_connect"))
    )
    (net (code "115") (name "unconnected-(U4-QH'-Pad9)") (class "Default")
      (node (ref "U4") (pin "9") (pinfunction "QH'_9") (pintype "unspecified+no_connect"))
    )
    (net (code "116") (name "unconnected-(U5-ALE{slash}P4.5-Pad30)") (class "Default")
      (node (ref "U5") (pin "30") (pinfunction "ALE/P4.5_30") (pintype "unspecified+no_connect"))
    )
    (net (code "117") (name "unconnected-(U5-INT1#{slash}P3.3-Pad13)") (class "Default")
      (node (ref "U5") (pin "13") (pinfunction "INT1#/P3.3_13") (pintype "unspecified+no_connect"))
    )
    (net (code "118") (name "unconnected-(U5-P0.0-Pad39)") (class "Default")
      (node (ref "U5") (pin "39") (pinfunction "P0.0_39") (pintype "unspecified+no_connect"))
    )
    (net (code "119") (name "unconnected-(U5-P0.1-Pad38)") (class "Default")
      (node (ref "U5") (pin "38") (pinfunction "P0.1_38") (pintype "unspecified+no_connect"))
    )
    (net (code "120") (name "unconnected-(U5-P0.2-Pad37)") (class "Default")
      (node (ref "U5") (pin "37") (pinfunction "P0.2_37") (pintype "unspecified+no_connect"))
    )
    (net (code "121") (name "unconnected-(U5-P0.3-Pad36)") (class "Default")
      (node (ref "U5") (pin "36") (pinfunction "P0.3_36") (pintype "unspecified+no_connect"))
    )
    (net (code "122") (name "unconnected-(U5-P0.4-Pad35)") (class "Default")
      (node (ref "U5") (pin "35") (pinfunction "P0.4_35") (pintype "unspecified+no_connect"))
    )
    (net (code "123") (name "unconnected-(U5-P0.5-Pad34)") (class "Default")
      (node (ref "U5") (pin "34") (pinfunction "P0.5_34") (pintype "unspecified+no_connect"))
    )
    (net (code "124") (name "unconnected-(U5-P0.6-Pad33)") (class "Default")
      (node (ref "U5") (pin "33") (pinfunction "P0.6_33") (pintype "unspecified+no_connect"))
    )
    (net (code "125") (name "unconnected-(U5-P0.7-Pad32)") (class "Default")
      (node (ref "U5") (pin "32") (pinfunction "P0.7_32") (pintype "unspecified+no_connect"))
    )
    (net (code "126") (name "unconnected-(U5-P1.2-Pad3)") (class "Default")
      (node (ref "U5") (pin "3") (pinfunction "P1.2_3") (pintype "unspecified+no_connect"))
    )
    (net (code "127") (name "unconnected-(U5-P1.3-Pad4)") (class "Default")
      (node (ref "U5") (pin "4") (pinfunction "P1.3_4") (pintype "unspecified+no_connect"))
    )
    (net (code "128") (name "unconnected-(U5-P1.4-Pad5)") (class "Default")
      (node (ref "U5") (pin "5") (pinfunction "P1.4_5") (pintype "unspecified+no_connect"))
    )
    (net (code "129") (name "unconnected-(U5-P1.5-Pad6)") (class "Default")
      (node (ref "U5") (pin "6") (pinfunction "P1.5_6") (pintype "unspecified+no_connect"))
    )
    (net (code "130") (name "unconnected-(U5-P1.6-Pad7)") (class "Default")
      (node (ref "U5") (pin "7") (pinfunction "P1.6_7") (pintype "unspecified+no_connect"))
    )
    (net (code "131") (name "unconnected-(U5-P1.7-Pad8)") (class "Default")
      (node (ref "U5") (pin "8") (pinfunction "P1.7_8") (pintype "unspecified+no_connect"))
    )
    (net (code "132") (name "unconnected-(U5-P2.1-Pad22)") (class "Default")
      (node (ref "U5") (pin "22") (pinfunction "P2.1_22") (pintype "unspecified+no_connect"))
    )
    (net (code "133") (name "unconnected-(U5-P2.3-Pad24)") (class "Default")
      (node (ref "U5") (pin "24") (pinfunction "P2.3_24") (pintype "unspecified+no_connect"))
    )
    (net (code "134") (name "unconnected-(U5-P2.5-Pad26)") (class "Default")
      (node (ref "U5") (pin "26") (pinfunction "P2.5_26") (pintype "unspecified+no_connect"))
    )
    (net (code "135") (name "unconnected-(U5-P2.6-Pad27)") (class "Default")
      (node (ref "U5") (pin "27") (pinfunction "P2.6_27") (pintype "unspecified+no_connect"))
    )
    (net (code "136") (name "unconnected-(U5-P2.7-Pad28)") (class "Default")
      (node (ref "U5") (pin "28") (pinfunction "P2.7_28") (pintype "unspecified+no_connect"))
    )
    (net (code "137") (name "unconnected-(U5-P4.4-Pad29)") (class "Default")
      (node (ref "U5") (pin "29") (pinfunction "P4.4_29") (pintype "unspecified+no_connect"))
    )
    (net (code "138") (name "unconnected-(U5-P4.6-Pad31)") (class "Default")
      (node (ref "U5") (pin "31") (pinfunction "P4.6_31") (pintype "unspecified+no_connect"))
    )
    (net (code "139") (name "unconnected-(U5-RD#{slash}P3.7-Pad17)") (class "Default")
      (node (ref "U5") (pin "17") (pinfunction "RD#/P3.7_17") (pintype "unspecified+no_connect"))
    )
    (net (code "140") (name "unconnected-(U5-RXD{slash}P3.0-Pad10)") (class "Default")
      (node (ref "U5") (pin "10") (pinfunction "RXD/P3.0_10") (pintype "unspecified+no_connect"))
    )
    (net (code "141") (name "unconnected-(U5-T0{slash}P3.4-Pad14)") (class "Default")
      (node (ref "U5") (pin "14") (pinfunction "T0/P3.4_14") (pintype "unspecified+no_connect"))
    )
    (net (code "142") (name "unconnected-(U5-T1{slash}P3.5-Pad15)") (class "Default")
      (node (ref "U5") (pin "15") (pinfunction "T1/P3.5_15") (pintype "unspecified+no_connect"))
    )
    (net (code "143") (name "unconnected-(U5-T2EX{slash}P1.1-Pad2)") (class "Default")
      (node (ref "U5") (pin "2") (pinfunction "T2EX/P1.1_2") (pintype "unspecified+no_connect"))
    )
    (net (code "144") (name "unconnected-(U5-T2{slash}P1.0-Pad1)") (class "Default")
      (node (ref "U5") (pin "1") (pinfunction "T2/P1.0_1") (pintype "unspecified+no_connect"))
    )
    (net (code "145") (name "unconnected-(U5-TXD{slash}P3.1-Pad11)") (class "Default")
      (node (ref "U5") (pin "11") (pinfunction "TXD/P3.1_11") (pintype "unspecified+no_connect"))
    )
    (net (code "146") (name "unconnected-(U5-WR#{slash}P3.6-Pad16)") (class "Default")
      (node (ref "U5") (pin "16") (pinfunction "WR#/P3.6_16") (pintype "unspecified+no_connect"))
    )
  )
)
